# Display-2023.net
KiCad netlist of a schematic drawn in EAGLE
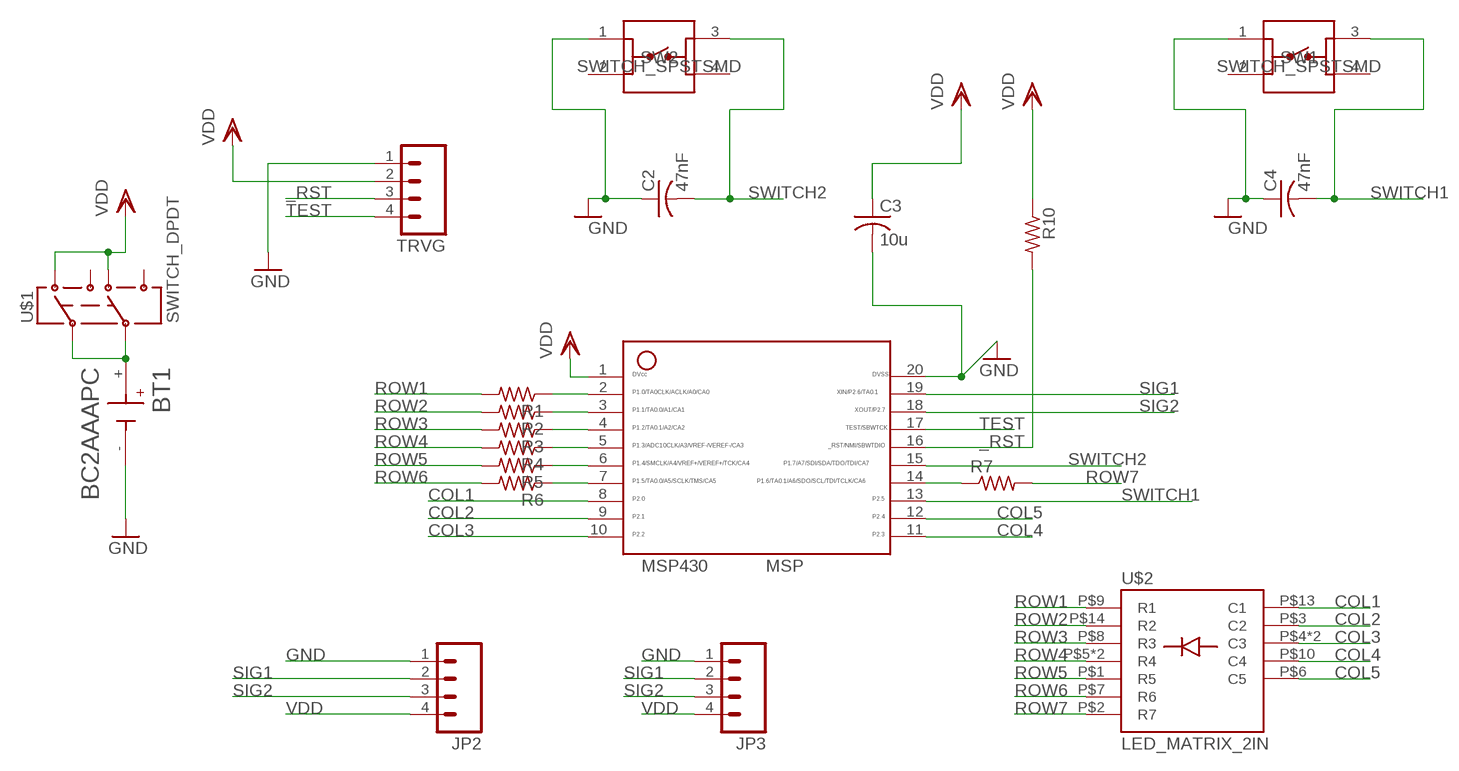
[diagram p0: schematic, sheet 1]

(export (version "E")
  (design (tool "Eeschema 10.0.6"))
  (components
    (comp (ref "BT1")
      (value "BC2AAAPC")
      (footprint "eagle-import:BAT_BC2AAAPC")
      (fields (field (name "DIGI-KEY_PART_NUMBER") "BC2AAAPC-ND") (field (name "MF") "MPD"))
      (libsource (lib "eagle-import") (part "BC2AAAPC"))
    )
    (comp (ref "C2")
      (value "47nF")
      (footprint "eagle-import:C0603")
      (libsource (lib "eagle-import") (part "C-USC0603"))
    )
    (comp (ref "C3")
      (value "10u")
      (footprint "eagle-import:C1206")
      (libsource (lib "eagle-import") (part "C-USC1206"))
    )
    (comp (ref "C4")
      (value "47nF")
      (footprint "eagle-import:C0603")
      (libsource (lib "eagle-import") (part "C-USC0603"))
    )
    (comp (ref "JP2")
      (value "M04LOCK")
      (footprint "eagle-import:1X04_LOCK")
      (libsource (lib "eagle-import") (part "M04LOCK"))
    )
    (comp (ref "JP3")
      (value "M04LOCK")
      (footprint "eagle-import:1X04_LOCK")
      (libsource (lib "eagle-import") (part "M04LOCK"))
    )
    (comp (ref "MSP430")
      (value "MSP")
      (footprint "eagle-import:20_PIN")
      (libsource (lib "eagle-import") (part "MSP430"))
    )
    (comp (ref "R1")
      (value "R-US_R0402")
      (footprint "eagle-import:R0402")
      (libsource (lib "eagle-import") (part "R-US_R0402"))
    )
    (comp (ref "R2")
      (value "R-US_R0402")
      (footprint "eagle-import:R0402")
      (libsource (lib "eagle-import") (part "R-US_R0402"))
    )
    (comp (ref "R3")
      (value "R-US_R0402")
      (footprint "eagle-import:R0402")
      (libsource (lib "eagle-import") (part "R-US_R0402"))
    )
    (comp (ref "R4")
      (value "R-US_R0402")
      (footprint "eagle-import:R0402")
      (libsource (lib "eagle-import") (part "R-US_R0402"))
    )
    (comp (ref "R5")
      (value "R-US_R0402")
      (footprint "eagle-import:R0402")
      (libsource (lib "eagle-import") (part "R-US_R0402"))
    )
    (comp (ref "R6")
      (value "R-US_R0402")
      (footprint "eagle-import:R0402")
      (libsource (lib "eagle-import") (part "R-US_R0402"))
    )
    (comp (ref "R7")
      (value "R-US_R0402")
      (footprint "eagle-import:R0402")
      (libsource (lib "eagle-import") (part "R-US_R0402"))
    )
    (comp (ref "R10")
      (value "R-US_R0402")
      (footprint "eagle-import:R0402")
      (libsource (lib "eagle-import") (part "R-US_R0402"))
    )
    (comp (ref "SW1")
      (value "SWITCH_SPSTSMD")
      (footprint "eagle-import:SW_1571563-4")
      (libsource (lib "eagle-import") (part "SWITCH_SPSTSMD"))
    )
    (comp (ref "SW2")
      (value "SWITCH_SPSTSMD")
      (footprint "eagle-import:SW_1571563-4")
      (libsource (lib "eagle-import") (part "SWITCH_SPSTSMD"))
    )
    (comp (ref "TRVG")
      (value "M04LOCK")
      (footprint "eagle-import:1X04_LOCK")
      (libsource (lib "eagle-import") (part "M04LOCK"))
    )
    (comp (ref "U$1")
      (value "SWITCH_DPDT")
      (footprint "eagle-import:JS_DPDT_TH")
      (libsource (lib "eagle-import") (part "SWITCH_DPDT"))
    )
    (comp (ref "U$2")
      (value "LED_MATRIX_2IN")
      (footprint "eagle-import:LED_MATRIX_5_7")
      (libsource (lib "eagle-import") (part "LED_MATRIX_2IN"))
    )
  )
  (nets
    (net (code "1") (name "COL1") (class "Default")
      (node (ref "MSP430") (pin "8") (pinfunction "8_8") (pintype "bidirectional"))
      (node (ref "U$2") (pin "P$13") (pinfunction "C1_P$13") (pintype "passive"))
    )
    (net (code "2") (name "COL2") (class "Default")
      (node (ref "MSP430") (pin "9") (pinfunction "9_9") (pintype "bidirectional"))
      (node (ref "U$2") (pin "P$3") (pinfunction "C2_P$3") (pintype "passive"))
    )
    (net (code "3") (name "COL3") (class "Default")
      (node (ref "MSP430") (pin "10") (pinfunction "10_10") (pintype "bidirectional"))
      (node (ref "U$2") (pin "P$11") (pinfunction "C3_P$11") (pintype "passive"))
      (node (ref "U$2") (pin "P$4") (pinfunction "C3_P$4") (pintype "passive"))
    )
    (net (code "4") (name "COL4") (class "Default")
      (node (ref "MSP430") (pin "11") (pinfunction "11_11") (pintype "bidirectional"))
      (node (ref "U$2") (pin "P$10") (pinfunction "C4_P$10") (pintype "passive"))
    )
    (net (code "5") (name "COL5") (class "Default")
      (node (ref "MSP430") (pin "12") (pinfunction "12_12") (pintype "bidirectional"))
      (node (ref "U$2") (pin "P$6") (pinfunction "C5_P$6") (pintype "passive"))
    )
    (net (code "6") (name "GND") (class "Default")
      (node (ref "BT1") (pin "-") (pinfunction "-_-") (pintype "passive"))
      (node (ref "C2") (pin "1") (pinfunction "1_1") (pintype "passive"))
      (node (ref "C3") (pin "2") (pinfunction "2_2") (pintype "passive"))
      (node (ref "C4") (pin "1") (pinfunction "1_1") (pintype "passive"))
      (node (ref "JP2") (pin "1") (pinfunction "1_1") (pintype "passive"))
      (node (ref "JP3") (pin "1") (pinfunction "1_1") (pintype "passive"))
      (node (ref "MSP430") (pin "20") (pinfunction "20_20") (pintype "bidirectional"))
      (node (ref "SW1") (pin "1") (pinfunction "1_1") (pintype "passive"))
      (node (ref "SW2") (pin "1") (pinfunction "1_1") (pintype "passive"))
      (node (ref "TRVG") (pin "1") (pinfunction "1_1") (pintype "passive"))
    )
    (net (code "7") (name "Net-(BT1-Pad+)") (class "Default")
      (node (ref "BT1") (pin "+") (pinfunction "+_+") (pintype "passive"))
      (node (ref "U$1") (pin "2") (pinfunction "2_2") (pintype "bidirectional"))
      (node (ref "U$1") (pin "5") (pinfunction "5_5") (pintype "bidirectional"))
    )
    (net (code "8") (name "Net-(MSP430-Pad2)") (class "Default")
      (node (ref "MSP430") (pin "2") (pinfunction "2_2") (pintype "bidirectional"))
      (node (ref "R1") (pin "1") (pinfunction "1_1") (pintype "passive"))
    )
    (net (code "9") (name "Net-(MSP430-Pad3)") (class "Default")
      (node (ref "MSP430") (pin "3") (pinfunction "3_3") (pintype "bidirectional"))
      (node (ref "R2") (pin "1") (pinfunction "1_1") (pintype "passive"))
    )
    (net (code "10") (name "Net-(MSP430-Pad4)") (class "Default")
      (node (ref "MSP430") (pin "4") (pinfunction "4_4") (pintype "bidirectional"))
      (node (ref "R3") (pin "1") (pinfunction "1_1") (pintype "passive"))
    )
    (net (code "11") (name "Net-(MSP430-Pad5)") (class "Default")
      (node (ref "MSP430") (pin "5") (pinfunction "5_5") (pintype "bidirectional"))
      (node (ref "R4") (pin "1") (pinfunction "1_1") (pintype "passive"))
    )
    (net (code "12") (name "Net-(MSP430-Pad6)") (class "Default")
      (node (ref "MSP430") (pin "6") (pinfunction "6_6") (pintype "bidirectional"))
      (node (ref "R5") (pin "1") (pinfunction "1_1") (pintype "passive"))
    )
    (net (code "13") (name "Net-(MSP430-Pad7)") (class "Default")
      (node (ref "MSP430") (pin "7") (pinfunction "7_7") (pintype "bidirectional"))
      (node (ref "R6") (pin "1") (pinfunction "1_1") (pintype "passive"))
    )
    (net (code "14") (name "Net-(MSP430-Pad14)") (class "Default")
      (node (ref "MSP430") (pin "14") (pinfunction "14_14") (pintype "bidirectional"))
      (node (ref "R7") (pin "1") (pinfunction "1_1") (pintype "passive"))
    )
    (net (code "15") (name "ROW1") (class "Default")
      (node (ref "R1") (pin "2") (pinfunction "2_2") (pintype "passive"))
      (node (ref "U$2") (pin "P$9") (pinfunction "R1_P$9") (pintype "passive"))
    )
    (net (code "16") (name "ROW2") (class "Default")
      (node (ref "R2") (pin "2") (pinfunction "2_2") (pintype "passive"))
      (node (ref "U$2") (pin "P$14") (pinfunction "R2_P$14") (pintype "passive"))
    )
    (net (code "17") (name "ROW3") (class "Default")
      (node (ref "R3") (pin "2") (pinfunction "2_2") (pintype "passive"))
      (node (ref "U$2") (pin "P$8") (pinfunction "R3_P$8") (pintype "passive"))
    )
    (net (code "18") (name "ROW4") (class "Default")
      (node (ref "R4") (pin "2") (pinfunction "2_2") (pintype "passive"))
      (node (ref "U$2") (pin "P$12") (pinfunction "R4_P$12") (pintype "passive"))
      (node (ref "U$2") (pin "P$5") (pinfunction "R4_P$5") (pintype "passive"))
    )
    (net (code "19") (name "ROW5") (class "Default")
      (node (ref "R5") (pin "2") (pinfunction "2_2") (pintype "passive"))
      (node (ref "U$2") (pin "P$1") (pinfunction "R5_P$1") (pintype "passive"))
    )
    (net (code "20") (name "ROW6") (class "Default")
      (node (ref "R6") (pin "2") (pinfunction "2_2") (pintype "passive"))
      (node (ref "U$2") (pin "P$7") (pinfunction "R6_P$7") (pintype "passive"))
    )
    (net (code "21") (name "ROW7") (class "Default")
      (node (ref "R7") (pin "2") (pinfunction "2_2") (pintype "passive"))
      (node (ref "U$2") (pin "P$2") (pinfunction "R7_P$2") (pintype "passive"))
    )
    (net (code "22") (name "SIG1") (class "Default")
      (node (ref "JP2") (pin "2") (pinfunction "2_2") (pintype "passive"))
      (node (ref "JP3") (pin "2") (pinfunction "2_2") (pintype "passive"))
      (node (ref "MSP430") (pin "19") (pinfunction "19_19") (pintype "bidirectional"))
    )
    (net (code "23") (name "SIG2") (class "Default")
      (node (ref "JP2") (pin "3") (pinfunction "3_3") (pintype "passive"))
      (node (ref "JP3") (pin "3") (pinfunction "3_3") (pintype "passive"))
      (node (ref "MSP430") (pin "18") (pinfunction "18_18") (pintype "bidirectional"))
    )
    (net (code "24") (name "SWITCH1") (class "Default")
      (node (ref "C4") (pin "2") (pinfunction "2_2") (pintype "passive"))
      (node (ref "MSP430") (pin "13") (pinfunction "13_13") (pintype "bidirectional"))
      (node (ref "SW1") (pin "3") (pinfunction "3_3") (pintype "passive"))
    )
    (net (code "25") (name "SWITCH2") (class "Default")
      (node (ref "C2") (pin "2") (pinfunction "2_2") (pintype "passive"))
      (node (ref "MSP430") (pin "15") (pinfunction "15_15") (pintype "bidirectional"))
      (node (ref "SW2") (pin "3") (pinfunction "3_3") (pintype "passive"))
    )
    (net (code "26") (name "TEST") (class "Default")
      (node (ref "MSP430") (pin "17") (pinfunction "17_17") (pintype "bidirectional"))
      (node (ref "TRVG") (pin "4") (pinfunction "4_4") (pintype "passive"))
    )
    (net (code "27") (name "VDD") (class "Default")
      (node (ref "C3") (pin "1") (pinfunction "1_1") (pintype "passive"))
      (node (ref "JP2") (pin "4") (pinfunction "4_4") (pintype "passive"))
      (node (ref "JP3") (pin "4") (pinfunction "4_4") (pintype "passive"))
      (node (ref "MSP430") (pin "1") (pinfunction "1_1") (pintype "bidirectional"))
      (node (ref "R10") (pin "1") (pinfunction "1_1") (pintype "passive"))
      (node (ref "TRVG") (pin "2") (pinfunction "2_2") (pintype "passive"))
      (node (ref "U$1") (pin "1") (pinfunction "1_1") (pintype "bidirectional"))
      (node (ref "U$1") (pin "4") (pinfunction "4_4") (pintype "bidirectional"))
    )
    (net (code "28") (name "_RST") (class "Default")
      (node (ref "MSP430") (pin "16") (pinfunction "16_16") (pintype "bidirectional"))
      (node (ref "R10") (pin "2") (pinfunction "2_2") (pintype "passive"))
      (node (ref "TRVG") (pin "3") (pinfunction "3_3") (pintype "passive"))
    )
    (net (code "29") (name "unconnected-(SW1-Pad2)") (class "Default")
      (node (ref "SW1") (pin "2") (pinfunction "2_2") (pintype "passive"))
    )
    (net (code "30") (name "unconnected-(SW1-Pad4)") (class "Default")
      (node (ref "SW1") (pin "4") (pinfunction "4_4") (pintype "passive"))
    )
    (net (code "31") (name "unconnected-(SW2-Pad2)") (class "Default")
      (node (ref "SW2") (pin "2") (pinfunction "2_2") (pintype "passive"))
    )
    (net (code "32") (name "unconnected-(SW2-Pad4)") (class "Default")
      (node (ref "SW2") (pin "4") (pinfunction "4_4") (pintype "passive"))
    )
    (net (code "33") (name "unconnected-(U$1-Pad3)") (class "Default")
      (node (ref "U$1") (pin "3") (pinfunction "3_3") (pintype "bidirectional"))
    )
    (net (code "34") (name "unconnected-(U$1-Pad6)") (class "Default")
      (node (ref "U$1") (pin "6") (pinfunction "6_6") (pintype "bidirectional"))
    )
  )
)
